# B01_IchigojamCap-Y_v1_0.net
KiCad netlist of a schematic drawn in EAGLE
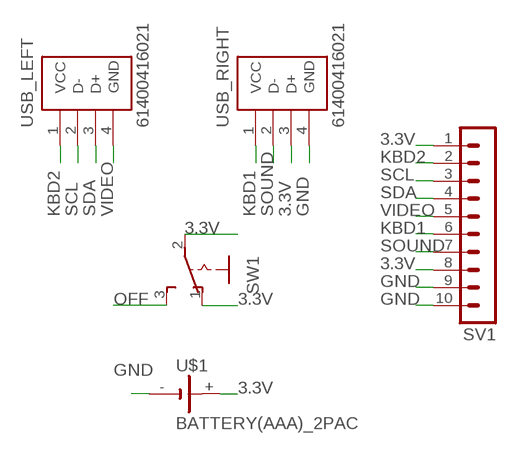
[diagram p0: schematic, sheet 1]

(export (version "E")
  (design (tool "Eeschema 10.0.6"))
  (components
    (comp (ref "SV1")
      (value "MA10-1")
      (footprint "eagle-import:MA10-1")
      (libsource (lib "eagle-import") (part "MA10-1"))
    )
    (comp (ref "SW1")
      (value "255SB")
      (footprint "eagle-import:255SB")
      (libsource (lib "eagle-import") (part "255SB"))
    )
    (comp (ref "U$1")
      (value "BATTERY(AAA)_2PAC")
      (footprint "eagle-import:BATTERY_HOLDER")
      (libsource (lib "eagle-import") (part "BATTERY(AAA)_2PAC"))
    )
    (comp (ref "USB_LEFT")
      (value "61400416021")
      (footprint "eagle-import:61400416021")
      (libsource (lib "eagle-import") (part "61400416021"))
    )
    (comp (ref "USB_RIGHT")
      (value "61400416021")
      (footprint "eagle-import:61400416021")
      (libsource (lib "eagle-import") (part "61400416021"))
    )
  )
  (nets
    (net (code "1") (name "/3.3V") (class "Default")
      (node (ref "SV1") (pin "1") (pinfunction "1_1") (pintype "passive"))
      (node (ref "SV1") (pin "8") (pinfunction "8_8") (pintype "passive"))
      (node (ref "SW1") (pin "1") (pinfunction "O_1") (pintype "passive"))
      (node (ref "SW1") (pin "2") (pinfunction "P_2") (pintype "passive"))
      (node (ref "U$1") (pin "+") (pinfunction "+_+") (pintype "passive"))
      (node (ref "USB_RIGHT") (pin "3") (pinfunction "D+_3") (pintype "passive"))
    )
    (net (code "2") (name "/GND") (class "Default")
      (node (ref "SV1") (pin "10") (pinfunction "10_10") (pintype "passive"))
      (node (ref "SV1") (pin "9") (pinfunction "9_9") (pintype "passive"))
      (node (ref "U$1") (pin "-") (pinfunction "-_-") (pintype "passive"))
      (node (ref "USB_RIGHT") (pin "4") (pinfunction "GND_4") (pintype "passive"))
    )
    (net (code "3") (name "/KBD1") (class "Default")
      (node (ref "SV1") (pin "6") (pinfunction "6_6") (pintype "passive"))
      (node (ref "USB_RIGHT") (pin "1") (pinfunction "VCC_1") (pintype "passive"))
    )
    (net (code "4") (name "/KBD2") (class "Default")
      (node (ref "SV1") (pin "2") (pinfunction "2_2") (pintype "passive"))
      (node (ref "USB_LEFT") (pin "1") (pinfunction "VCC_1") (pintype "passive"))
    )
    (net (code "5") (name "/OFF") (class "Default")
      (node (ref "SW1") (pin "3") (pinfunction "S_3") (pintype "passive"))
    )
    (net (code "6") (name "/SCL") (class "Default")
      (node (ref "SV1") (pin "3") (pinfunction "3_3") (pintype "passive"))
      (node (ref "USB_LEFT") (pin "2") (pinfunction "D-_2") (pintype "passive"))
    )
    (net (code "7") (name "/SDA") (class "Default")
      (node (ref "SV1") (pin "4") (pinfunction "4_4") (pintype "passive"))
      (node (ref "USB_LEFT") (pin "3") (pinfunction "D+_3") (pintype "passive"))
    )
    (net (code "8") (name "/SOUND") (class "Default")
      (node (ref "SV1") (pin "7") (pinfunction "7_7") (pintype "passive"))
      (node (ref "USB_RIGHT") (pin "2") (pinfunction "D-_2") (pintype "passive"))
    )
    (net (code "9") (name "/VIDEO") (class "Default")
      (node (ref "SV1") (pin "5") (pinfunction "5_5") (pintype "passive"))
      (node (ref "USB_LEFT") (pin "4") (pinfunction "GND_4") (pintype "passive"))
    )
  )
)
